# vme_full_bus.net
KiCad netlist of a schematic drawn in Altium Designer
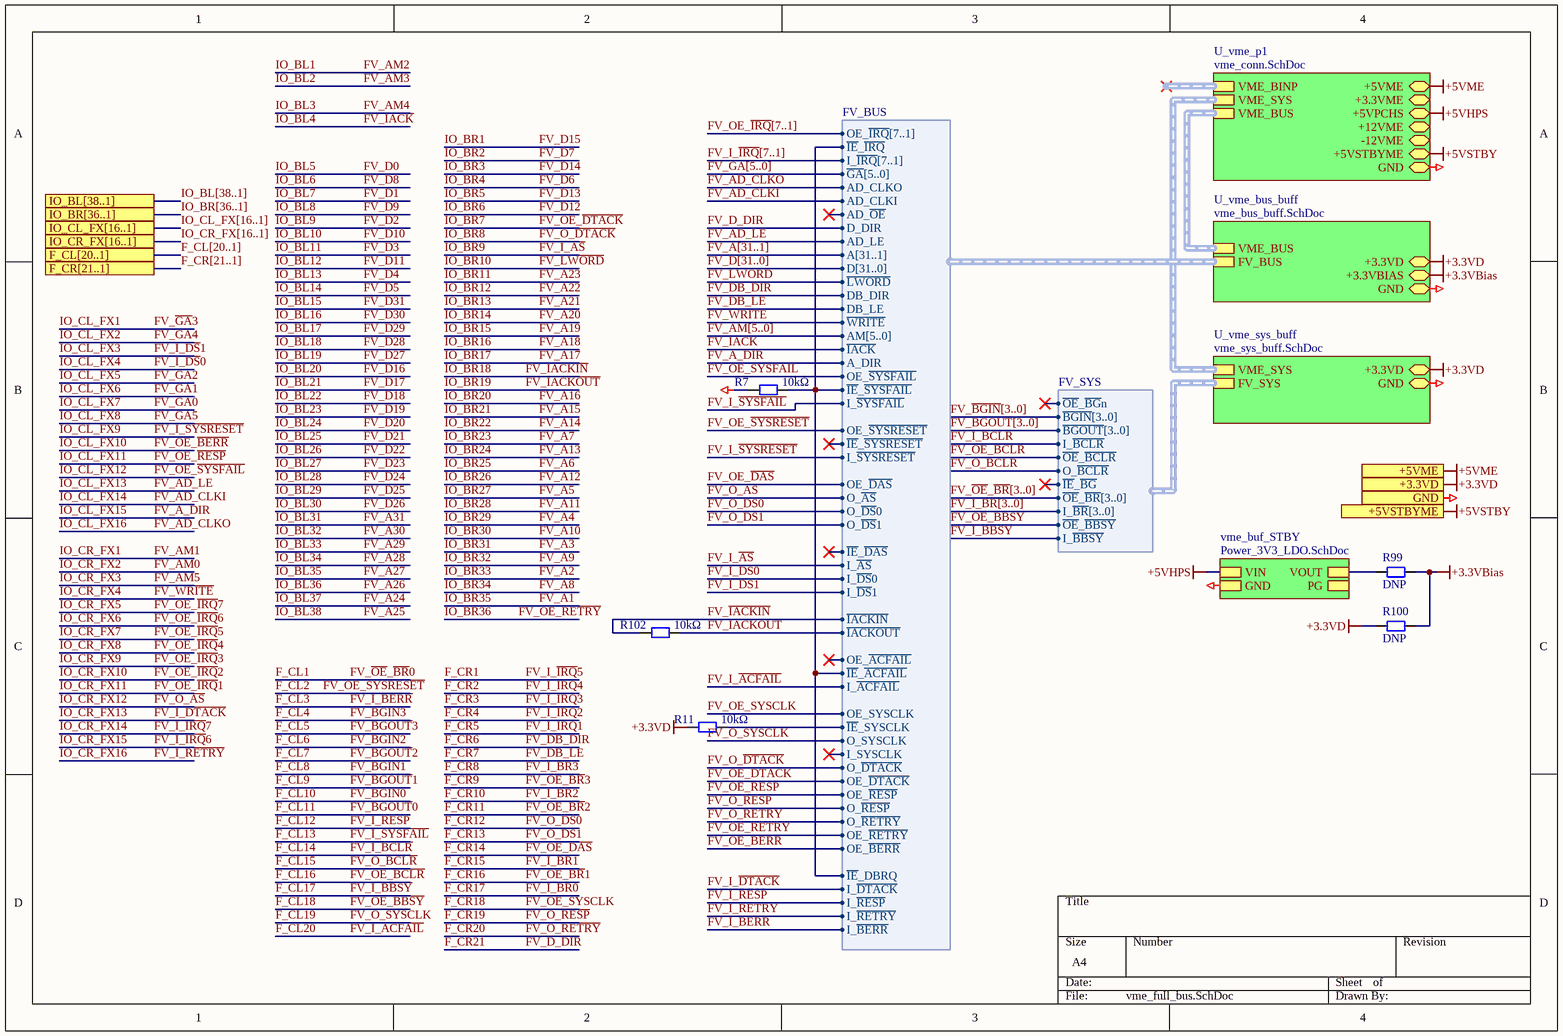
[diagram p0: vme_full_bus.SchDoc]

(export (version "E")
  (design (tool "Eeschema 10.0.6"))
  (components
    (comp (ref "R7")
      (value "10kΩ")
      (footprint "RESC2012N")
      (description "Resistor, Generic, SMD")
      (fields (field (name "MAINTAINER") "Evgeniy Kotov"))
      (libsource (lib "[Resistors] Resistors SMD") (part "RESC"))
    )
    (comp (ref "R11")
      (value "10kΩ")
      (footprint "RESC2012N")
      (description "Resistor, Generic, SMD")
      (fields (field (name "MAINTAINER") "Evgeniy Kotov"))
      (libsource (lib "[Resistors] Resistors SMD") (part "RESC"))
    )
    (comp (ref "R99")
      (value "DNP")
      (footprint "RESC2012N")
      (description "Resistor, Generic, SMD")
      (fields (field (name "MAINTAINER") "Evgeniy Kotov"))
      (libsource (lib "[Resistors] Resistors SMD") (part "RESC"))
    )
    (comp (ref "R100")
      (value "DNP")
      (footprint "RESC2012N")
      (description "Resistor, Generic, SMD")
      (fields (field (name "MAINTAINER") "Evgeniy Kotov"))
      (libsource (lib "[Resistors] Resistors SMD") (part "RESC"))
    )
    (comp (ref "R102")
      (value "10kΩ")
      (footprint "RESC2012N")
      (description "Resistor, Generic, SMD")
      (fields (field (name "MAINTAINER") "Evgeniy Kotov"))
      (libsource (lib "[Resistors] Resistors SMD") (part "RESC"))
    )
  )
  (nets
    (net (code "2") (name "+3.3VBias") (class "Default")
      (node (ref "R100") (pin "2") (pintype "passive"))
      (node (ref "R99") (pin "2") (pintype "passive"))
    )
    (net (code "3") (name "+3.3VD") (class "Default")
      (node (ref "R100") (pin "1") (pintype "passive"))
      (node (ref "R11") (pin "1") (pintype "passive"))
    )
    (net (code "120") (name "/IO_BR18") (class "Default") (node (ref "R102") (pin "1") (pintype "passive")))
    (net (code "121") (name "/IO_BR19") (class "Default") (node (ref "R102") (pin "2") (pintype "passive")))
    (net (code "180") (name "/VOUT") (class "Default") (node (ref "R99") (pin "1") (pintype "passive")))
    (net (code "183") (name "/~{IE}_DBRQ") (class "Default") (node (ref "R7") (pin "2") (pintype "passive")))
    (net (code "184") (name "/~{IE}_SYSCLK") (class "Default")
      (node (ref "R11") (pin "2") (pintype "passive"))
    )
    (net (code "189") (name "GND") (class "Default") (node (ref "R7") (pin "1") (pintype "passive")))
  )
)
